# Main.net
KiCad netlist of a schematic drawn in Altium Designer
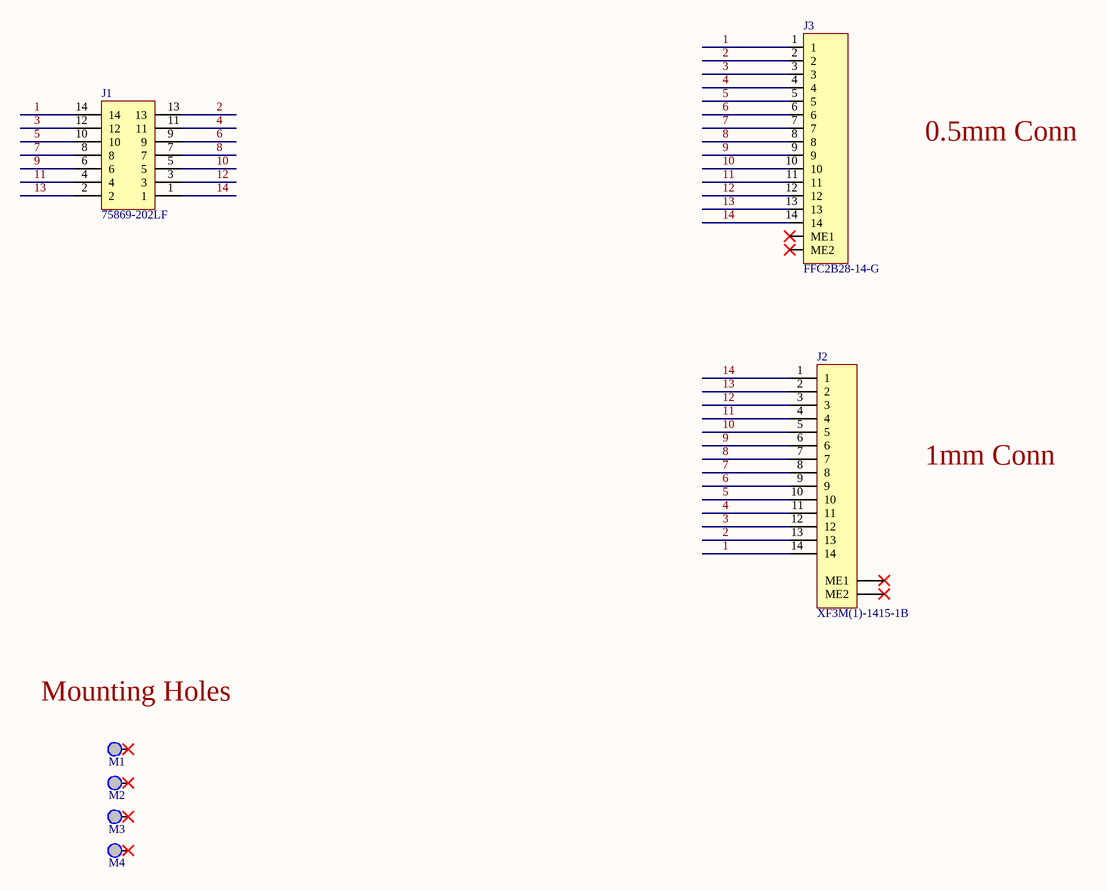
[diagram p0: Main.SchDoc]

(export (version "E")
  (design (tool "Eeschema 10.0.6"))
  (components
    (comp (ref "J1")
      (value "75869-202LF")
      (footprint "HDR-V-2x7-KEYED")
      (description "Headers & Wire Housings 14P DR VERT SHRD HDR TIN")
      (libsource (lib "intercreate") (part "HDR-V-2x7-M"))
    )
    (comp (ref "J2")
      (value "XF3M(1)-1415-1B")
      (footprint "CONN-FFC-H-14P-1MM")
      (description "1.0-mm Pitch, Dual Contact ; For FPC/FFC, 14 Contacts, RoHS")
      (libsource (lib "intercreate") (part "CONN-FFC-H-14P-1MM"))
    )
    (comp (ref "J3")
      (value "FFC2B28-14-G")
      (footprint "CONN-FFC-H-14P-0.5MM")
      (description "14W, 0.5MM Ffc Con, R/a, Dual Cont,")
      (libsource (lib "intercreate") (part "CONN-FFC-H-14P-0.5MM"))
    )
    (comp (ref "M1")
      (value "MTG_HOLE")
      (footprint "MH_P_2.5MM")
      (description "MTG HOLE PLATED VARIOUS SIZES")
      (libsource (lib "intercreate") (part "MTG_HOLE"))
    )
    (comp (ref "M2")
      (value "MTG_HOLE")
      (footprint "MH_P_2.5MM")
      (description "MTG HOLE PLATED VARIOUS SIZES")
      (libsource (lib "intercreate") (part "MTG_HOLE"))
    )
    (comp (ref "M3")
      (value "MTG_HOLE")
      (footprint "MH_P_2.5MM")
      (description "MTG HOLE PLATED VARIOUS SIZES")
      (libsource (lib "intercreate") (part "MTG_HOLE"))
    )
    (comp (ref "M4")
      (value "MTG_HOLE")
      (footprint "MH_P_2.5MM")
      (description "MTG HOLE PLATED VARIOUS SIZES")
      (libsource (lib "intercreate") (part "MTG_HOLE"))
    )
  )
  (nets
    (net (code "1") (name "/1") (class "Default")
      (node (ref "J1") (pin "14") (pinfunction "14_14") (pintype "power_in"))
      (node (ref "J2") (pin "14") (pinfunction "14_14") (pintype "passive"))
      (node (ref "J3") (pin "1") (pinfunction "1_1") (pintype "passive"))
    )
    (net (code "2") (name "/2") (class "Default")
      (node (ref "J1") (pin "13") (pinfunction "13_13") (pintype "power_in"))
      (node (ref "J2") (pin "13") (pinfunction "13_13") (pintype "passive"))
      (node (ref "J3") (pin "2") (pinfunction "2_2") (pintype "passive"))
    )
    (net (code "3") (name "/3") (class "Default")
      (node (ref "J1") (pin "12") (pinfunction "12_12") (pintype "power_in"))
      (node (ref "J2") (pin "12") (pinfunction "12_12") (pintype "passive"))
      (node (ref "J3") (pin "3") (pinfunction "3_3") (pintype "passive"))
    )
    (net (code "4") (name "/4") (class "Default")
      (node (ref "J1") (pin "11") (pinfunction "11_11") (pintype "power_in"))
      (node (ref "J2") (pin "11") (pinfunction "11_11") (pintype "passive"))
      (node (ref "J3") (pin "4") (pinfunction "4_4") (pintype "passive"))
    )
    (net (code "5") (name "/5") (class "Default")
      (node (ref "J1") (pin "10") (pinfunction "10_10") (pintype "passive"))
      (node (ref "J2") (pin "10") (pinfunction "10_10") (pintype "passive"))
      (node (ref "J3") (pin "5") (pinfunction "5_5") (pintype "passive"))
    )
    (net (code "6") (name "/6") (class "Default")
      (node (ref "J1") (pin "9") (pinfunction "9_9") (pintype "passive"))
      (node (ref "J2") (pin "9") (pinfunction "9_9") (pintype "passive"))
      (node (ref "J3") (pin "6") (pinfunction "6_6") (pintype "passive"))
    )
    (net (code "7") (name "/7") (class "Default")
      (node (ref "J1") (pin "8") (pinfunction "8_8") (pintype "passive"))
      (node (ref "J2") (pin "8") (pinfunction "8_8") (pintype "passive"))
      (node (ref "J3") (pin "7") (pinfunction "7_7") (pintype "passive"))
    )
    (net (code "8") (name "/8") (class "Default")
      (node (ref "J1") (pin "7") (pinfunction "7_7") (pintype "passive"))
      (node (ref "J2") (pin "7") (pinfunction "7_7") (pintype "passive"))
      (node (ref "J3") (pin "8") (pinfunction "8_8") (pintype "passive"))
    )
    (net (code "9") (name "/9") (class "Default")
      (node (ref "J1") (pin "6") (pinfunction "6_6") (pintype "passive"))
      (node (ref "J2") (pin "6") (pinfunction "6_6") (pintype "passive"))
      (node (ref "J3") (pin "9") (pinfunction "9_9") (pintype "passive"))
    )
    (net (code "10") (name "/10") (class "Default")
      (node (ref "J1") (pin "5") (pinfunction "5_5") (pintype "passive"))
      (node (ref "J2") (pin "5") (pinfunction "5_5") (pintype "passive"))
      (node (ref "J3") (pin "10") (pinfunction "10_10") (pintype "passive"))
    )
    (net (code "11") (name "/11") (class "Default")
      (node (ref "J1") (pin "4") (pinfunction "4_4") (pintype "passive"))
      (node (ref "J2") (pin "4") (pinfunction "4_4") (pintype "passive"))
      (node (ref "J3") (pin "11") (pinfunction "11_11") (pintype "passive"))
    )
    (net (code "12") (name "/12") (class "Default")
      (node (ref "J1") (pin "3") (pinfunction "3_3") (pintype "passive"))
      (node (ref "J2") (pin "3") (pinfunction "3_3") (pintype "passive"))
      (node (ref "J3") (pin "12") (pinfunction "12_12") (pintype "passive"))
    )
    (net (code "13") (name "/13") (class "Default")
      (node (ref "J1") (pin "2") (pinfunction "2_2") (pintype "passive"))
      (node (ref "J2") (pin "2") (pinfunction "2_2") (pintype "passive"))
      (node (ref "J3") (pin "13") (pinfunction "13_13") (pintype "passive"))
    )
    (net (code "14") (name "/14") (class "Default")
      (node (ref "J1") (pin "1") (pinfunction "1_1") (pintype "passive"))
      (node (ref "J2") (pin "1") (pinfunction "1_1") (pintype "passive"))
      (node (ref "J3") (pin "14") (pinfunction "14_14") (pintype "passive"))
    )
    (net (code "15") (name "unconnected-(J2-PadME1)") (class "Default")
      (node (ref "J2") (pin "ME1") (pinfunction "ME1_ME1") (pintype "passive+no_connect"))
    )
    (net (code "16") (name "unconnected-(J2-PadME2)") (class "Default")
      (node (ref "J2") (pin "ME2") (pinfunction "ME2_ME2") (pintype "passive+no_connect"))
    )
    (net (code "17") (name "unconnected-(J3-PadME1)") (class "Default")
      (node (ref "J3") (pin "ME1") (pinfunction "ME1_ME1") (pintype "passive+no_connect"))
    )
    (net (code "18") (name "unconnected-(J3-PadME2)") (class "Default")
      (node (ref "J3") (pin "ME2") (pinfunction "ME2_ME2") (pintype "passive+no_connect"))
    )
    (net (code "19") (name "unconnected-(M1-Pad1)") (class "Default")
      (node (ref "M1") (pin "1") (pinfunction "1_1") (pintype "passive+no_connect"))
    )
    (net (code "20") (name "unconnected-(M2-Pad1)") (class "Default")
      (node (ref "M2") (pin "1") (pinfunction "1_1") (pintype "passive+no_connect"))
    )
    (net (code "21") (name "unconnected-(M3-Pad1)") (class "Default")
      (node (ref "M3") (pin "1") (pinfunction "1_1") (pintype "passive+no_connect"))
    )
    (net (code "22") (name "unconnected-(M4-Pad1)") (class "Default")
      (node (ref "M4") (pin "1") (pinfunction "1_1") (pintype "passive+no_connect"))
    )
  )
)
